# placa_potencia.net
KiCad netlist of a schematic drawn in EAGLE
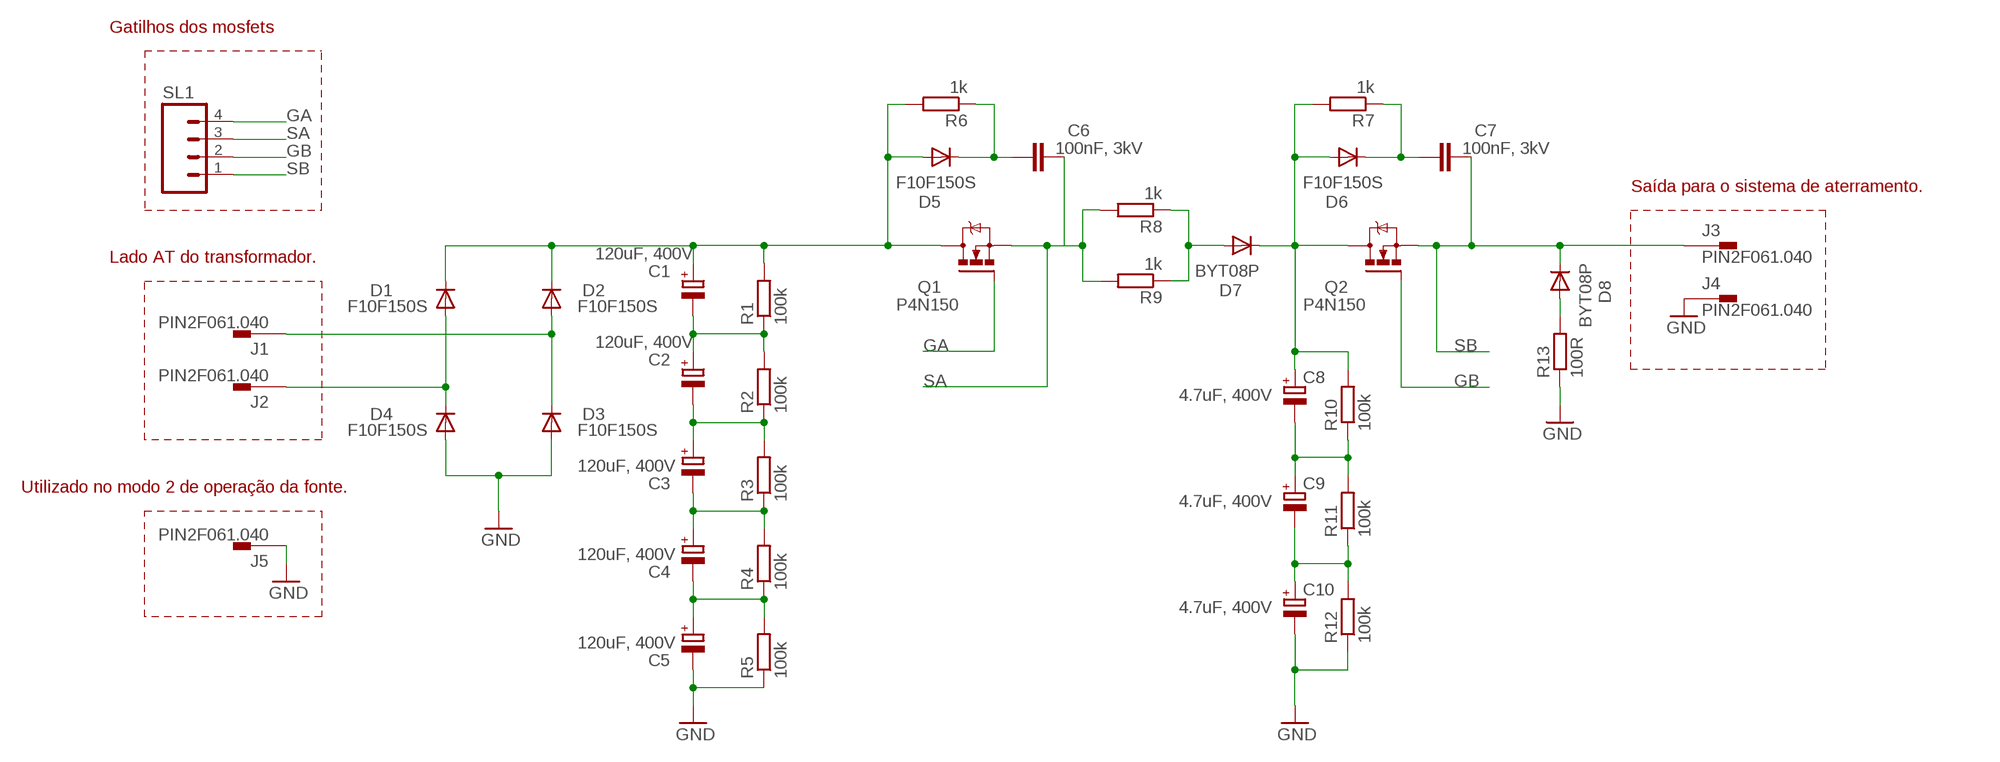
[diagram p0: schematic, sheet 1]

(export (version "E")
  (design (tool "Eeschema 10.0.6"))
  (components
    (comp (ref "C1")
      (value "120uF, 400V")
      (footprint "eagle-import:E7,5-16")
      (libsource (lib "eagle-import") (part "CPOL-EUE7.5-16"))
    )
    (comp (ref "C2")
      (value "120uF, 400V")
      (footprint "eagle-import:E7,5-16")
      (libsource (lib "eagle-import") (part "CPOL-EUE7.5-16"))
    )
    (comp (ref "C3")
      (value "120uF, 400V")
      (footprint "eagle-import:E7,5-16")
      (libsource (lib "eagle-import") (part "CPOL-EUE7.5-16"))
    )
    (comp (ref "C4")
      (value "120uF, 400V")
      (footprint "eagle-import:E7,5-16")
      (libsource (lib "eagle-import") (part "CPOL-EUE7.5-16"))
    )
    (comp (ref "C5")
      (value "120uF, 400V")
      (footprint "eagle-import:E7,5-16")
      (libsource (lib "eagle-import") (part "CPOL-EUE7.5-16"))
    )
    (comp (ref "C6")
      (value "100nF, 3kV")
      (footprint "eagle-import:C050-035X075")
      (libsource (lib "eagle-import") (part "C-EU050-035X075"))
    )
    (comp (ref "C7")
      (value "100nF, 3kV")
      (footprint "eagle-import:C050-035X075")
      (libsource (lib "eagle-import") (part "C-EU050-035X075"))
    )
    (comp (ref "C8")
      (value "4.7uF, 400V")
      (footprint "eagle-import:E5-8,5")
      (libsource (lib "eagle-import") (part "CPOL-EUE5-8.5"))
    )
    (comp (ref "C9")
      (value "4.7uF, 400V")
      (footprint "eagle-import:E5-8,5")
      (libsource (lib "eagle-import") (part "CPOL-EUE5-8.5"))
    )
    (comp (ref "C10")
      (value "4.7uF, 400V")
      (footprint "eagle-import:E5-8,5")
      (libsource (lib "eagle-import") (part "CPOL-EUE5-8.5"))
    )
    (comp (ref "D1")
      (value "F10F150S")
      (footprint "eagle-import:TO220ACS")
      (libsource (lib "eagle-import") (part "BYT08P"))
    )
    (comp (ref "D2")
      (value "F10F150S")
      (footprint "eagle-import:TO220ACS")
      (libsource (lib "eagle-import") (part "BYT08P"))
    )
    (comp (ref "D3")
      (value "F10F150S")
      (footprint "eagle-import:TO220ACS")
      (libsource (lib "eagle-import") (part "BYT08P"))
    )
    (comp (ref "D4")
      (value "F10F150S")
      (footprint "eagle-import:TO220ACS")
      (libsource (lib "eagle-import") (part "BYT08P"))
    )
    (comp (ref "D5")
      (value "F10F150S")
      (footprint "eagle-import:TO220ACS")
      (libsource (lib "eagle-import") (part "BYT08P"))
    )
    (comp (ref "D6")
      (value "F10F150S")
      (footprint "eagle-import:TO220ACS")
      (libsource (lib "eagle-import") (part "BYT08P"))
    )
    (comp (ref "D7")
      (value "BYT08P")
      (footprint "eagle-import:TO220ACS")
      (libsource (lib "eagle-import") (part "BYT08P"))
    )
    (comp (ref "D8")
      (value "BYT08P")
      (footprint "eagle-import:TO220ACS")
      (libsource (lib "eagle-import") (part "BYT08P"))
    )
    (comp (ref "J1")
      (value "PIN2F061.040")
      (footprint "eagle-import:F061.040")
      (libsource (lib "eagle-import") (part "PIN2F061.040"))
    )
    (comp (ref "J2")
      (value "PIN2F061.040")
      (footprint "eagle-import:F061.040")
      (libsource (lib "eagle-import") (part "PIN2F061.040"))
    )
    (comp (ref "J3")
      (value "PIN2F061.040")
      (footprint "eagle-import:F061.040")
      (libsource (lib "eagle-import") (part "PIN2F061.040"))
    )
    (comp (ref "J4")
      (value "PIN2F061.040")
      (footprint "eagle-import:F061.040")
      (libsource (lib "eagle-import") (part "PIN2F061.040"))
    )
    (comp (ref "J5")
      (value "PIN2F061.040")
      (footprint "eagle-import:F061.040")
      (libsource (lib "eagle-import") (part "PIN2F061.040"))
    )
    (comp (ref "Q1")
      (value "P4N150")
      (footprint "eagle-import:TO220BV")
      (libsource (lib "eagle-import") (part "IRF520"))
    )
    (comp (ref "Q2")
      (value "P4N150")
      (footprint "eagle-import:TO220BV")
      (libsource (lib "eagle-import") (part "IRF520"))
    )
    (comp (ref "R1")
      (value "100k")
      (footprint "eagle-import:0617_22")
      (libsource (lib "eagle-import") (part "R-EU_0617/22"))
    )
    (comp (ref "R2")
      (value "100k")
      (footprint "eagle-import:0617_22")
      (libsource (lib "eagle-import") (part "R-EU_0617/22"))
    )
    (comp (ref "R3")
      (value "100k")
      (footprint "eagle-import:0617_22")
      (libsource (lib "eagle-import") (part "R-EU_0617/22"))
    )
    (comp (ref "R4")
      (value "100k")
      (footprint "eagle-import:0617_22")
      (libsource (lib "eagle-import") (part "R-EU_0617/22"))
    )
    (comp (ref "R5")
      (value "100k")
      (footprint "eagle-import:0617_22")
      (libsource (lib "eagle-import") (part "R-EU_0617/22"))
    )
    (comp (ref "R6")
      (value "1k")
      (footprint "eagle-import:0617_22")
      (libsource (lib "eagle-import") (part "R-EU_0617/22"))
    )
    (comp (ref "R7")
      (value "1k")
      (footprint "eagle-import:0617_22")
      (libsource (lib "eagle-import") (part "R-EU_0617/22"))
    )
    (comp (ref "R8")
      (value "1k")
      (footprint "eagle-import:0617_22")
      (libsource (lib "eagle-import") (part "R-EU_0617/22"))
    )
    (comp (ref "R9")
      (value "1k")
      (footprint "eagle-import:0617_22")
      (libsource (lib "eagle-import") (part "R-EU_0617/22"))
    )
    (comp (ref "R10")
      (value "100k")
      (footprint "eagle-import:0617_22")
      (libsource (lib "eagle-import") (part "R-EU_0617/22"))
    )
    (comp (ref "R11")
      (value "100k")
      (footprint "eagle-import:0617_22")
      (libsource (lib "eagle-import") (part "R-EU_0617/22"))
    )
    (comp (ref "R12")
      (value "100k")
      (footprint "eagle-import:0617_22")
      (libsource (lib "eagle-import") (part "R-EU_0617/22"))
    )
    (comp (ref "R13")
      (value "100R")
      (footprint "eagle-import:0617_22")
      (libsource (lib "eagle-import") (part "R-EU_0617/22"))
    )
    (comp (ref "SL1")
      (value "M04")
      (footprint "eagle-import:04P")
      (libsource (lib "eagle-import") (part "M04"))
    )
  )
  (nets
    (net (code "1") (name "/GA") (class "Default")
      (node (ref "Q1") (pin "G") (pinfunction "G_G") (pintype "passive"))
      (node (ref "SL1") (pin "4") (pinfunction "4_4") (pintype "passive"))
    )
    (net (code "2") (name "/GB") (class "Default")
      (node (ref "Q2") (pin "G") (pinfunction "G_G") (pintype "passive"))
      (node (ref "SL1") (pin "2") (pinfunction "2_2") (pintype "passive"))
    )
    (net (code "3") (name "/SA") (class "Default")
      (node (ref "C6") (pin "2") (pinfunction "2_2") (pintype "passive"))
      (node (ref "Q1") (pin "S") (pinfunction "S_S") (pintype "passive"))
      (node (ref "R8") (pin "2") (pinfunction "2_2") (pintype "passive"))
      (node (ref "R9") (pin "2") (pinfunction "2_2") (pintype "passive"))
      (node (ref "SL1") (pin "3") (pinfunction "3_3") (pintype "passive"))
    )
    (net (code "4") (name "/SB") (class "Default")
      (node (ref "C7") (pin "2") (pinfunction "2_2") (pintype "passive"))
      (node (ref "D8") (pin "C") (pinfunction "C_C") (pintype "passive"))
      (node (ref "J3") (pin "A1") (pinfunction "1_A1") (pintype "passive"))
      (node (ref "J3") (pin "A2") (pinfunction "1_A2") (pintype "passive"))
      (node (ref "Q2") (pin "S") (pinfunction "S_S") (pintype "passive"))
      (node (ref "SL1") (pin "1") (pinfunction "1_1") (pintype "passive"))
    )
    (net (code "5") (name "GND") (class "Default")
      (node (ref "C10") (pin "-") (pinfunction "-_-") (pintype "passive"))
      (node (ref "C5") (pin "-") (pinfunction "-_-") (pintype "passive"))
      (node (ref "D3") (pin "A") (pinfunction "A_A") (pintype "passive"))
      (node (ref "D4") (pin "A") (pinfunction "A_A") (pintype "passive"))
      (node (ref "J4") (pin "A1") (pinfunction "1_A1") (pintype "passive"))
      (node (ref "J4") (pin "A2") (pinfunction "1_A2") (pintype "passive"))
      (node (ref "J5") (pin "A1") (pinfunction "1_A1") (pintype "passive"))
      (node (ref "J5") (pin "A2") (pinfunction "1_A2") (pintype "passive"))
      (node (ref "R12") (pin "1") (pinfunction "1_1") (pintype "passive"))
      (node (ref "R13") (pin "1") (pinfunction "1_1") (pintype "passive"))
      (node (ref "R5") (pin "1") (pinfunction "1_1") (pintype "passive"))
    )
    (net (code "6") (name "Net-(C1-Pad+)") (class "Default")
      (node (ref "C1") (pin "+") (pinfunction "+_+") (pintype "passive"))
      (node (ref "D1") (pin "C") (pinfunction "C_C") (pintype "passive"))
      (node (ref "D2") (pin "C") (pinfunction "C_C") (pintype "passive"))
      (node (ref "D5") (pin "A") (pinfunction "A_A") (pintype "passive"))
      (node (ref "Q1") (pin "D") (pinfunction "D_D") (pintype "passive"))
      (node (ref "R1") (pin "2") (pinfunction "2_2") (pintype "passive"))
      (node (ref "R6") (pin "2") (pinfunction "2_2") (pintype "passive"))
    )
    (net (code "7") (name "Net-(C1-Pad-)") (class "Default")
      (node (ref "C1") (pin "-") (pinfunction "-_-") (pintype "passive"))
      (node (ref "C2") (pin "+") (pinfunction "+_+") (pintype "passive"))
      (node (ref "R1") (pin "1") (pinfunction "1_1") (pintype "passive"))
      (node (ref "R2") (pin "2") (pinfunction "2_2") (pintype "passive"))
    )
    (net (code "8") (name "Net-(C2-Pad-)") (class "Default")
      (node (ref "C2") (pin "-") (pinfunction "-_-") (pintype "passive"))
      (node (ref "C3") (pin "+") (pinfunction "+_+") (pintype "passive"))
      (node (ref "R2") (pin "1") (pinfunction "1_1") (pintype "passive"))
      (node (ref "R3") (pin "2") (pinfunction "2_2") (pintype "passive"))
    )
    (net (code "9") (name "Net-(C3-Pad-)") (class "Default")
      (node (ref "C3") (pin "-") (pinfunction "-_-") (pintype "passive"))
      (node (ref "C4") (pin "+") (pinfunction "+_+") (pintype "passive"))
      (node (ref "R3") (pin "1") (pinfunction "1_1") (pintype "passive"))
      (node (ref "R4") (pin "2") (pinfunction "2_2") (pintype "passive"))
    )
    (net (code "10") (name "Net-(C4-Pad-)") (class "Default")
      (node (ref "C4") (pin "-") (pinfunction "-_-") (pintype "passive"))
      (node (ref "C5") (pin "+") (pinfunction "+_+") (pintype "passive"))
      (node (ref "R4") (pin "1") (pinfunction "1_1") (pintype "passive"))
      (node (ref "R5") (pin "2") (pinfunction "2_2") (pintype "passive"))
    )
    (net (code "11") (name "Net-(C6-Pad1)") (class "Default")
      (node (ref "C6") (pin "1") (pinfunction "1_1") (pintype "passive"))
      (node (ref "D5") (pin "C") (pinfunction "C_C") (pintype "passive"))
      (node (ref "R6") (pin "1") (pinfunction "1_1") (pintype "passive"))
    )
    (net (code "12") (name "Net-(C7-Pad1)") (class "Default")
      (node (ref "C7") (pin "1") (pinfunction "1_1") (pintype "passive"))
      (node (ref "D6") (pin "C") (pinfunction "C_C") (pintype "passive"))
      (node (ref "R7") (pin "1") (pinfunction "1_1") (pintype "passive"))
    )
    (net (code "13") (name "Net-(C8-Pad+)") (class "Default")
      (node (ref "C8") (pin "+") (pinfunction "+_+") (pintype "passive"))
      (node (ref "D6") (pin "A") (pinfunction "A_A") (pintype "passive"))
      (node (ref "D7") (pin "C") (pinfunction "C_C") (pintype "passive"))
      (node (ref "Q2") (pin "D") (pinfunction "D_D") (pintype "passive"))
      (node (ref "R10") (pin "2") (pinfunction "2_2") (pintype "passive"))
      (node (ref "R7") (pin "2") (pinfunction "2_2") (pintype "passive"))
    )
    (net (code "14") (name "Net-(C8-Pad-)") (class "Default")
      (node (ref "C8") (pin "-") (pinfunction "-_-") (pintype "passive"))
      (node (ref "C9") (pin "+") (pinfunction "+_+") (pintype "passive"))
      (node (ref "R10") (pin "1") (pinfunction "1_1") (pintype "passive"))
      (node (ref "R11") (pin "2") (pinfunction "2_2") (pintype "passive"))
    )
    (net (code "15") (name "Net-(C10-Pad+)") (class "Default")
      (node (ref "C10") (pin "+") (pinfunction "+_+") (pintype "passive"))
      (node (ref "C9") (pin "-") (pinfunction "-_-") (pintype "passive"))
      (node (ref "R11") (pin "1") (pinfunction "1_1") (pintype "passive"))
      (node (ref "R12") (pin "2") (pinfunction "2_2") (pintype "passive"))
    )
    (net (code "16") (name "Net-(D1-PadA)") (class "Default")
      (node (ref "D1") (pin "A") (pinfunction "A_A") (pintype "passive"))
      (node (ref "D4") (pin "C") (pinfunction "C_C") (pintype "passive"))
      (node (ref "J2") (pin "A1") (pinfunction "1_A1") (pintype "passive"))
      (node (ref "J2") (pin "A2") (pinfunction "1_A2") (pintype "passive"))
    )
    (net (code "17") (name "Net-(D2-PadA)") (class "Default")
      (node (ref "D2") (pin "A") (pinfunction "A_A") (pintype "passive"))
      (node (ref "D3") (pin "C") (pinfunction "C_C") (pintype "passive"))
      (node (ref "J1") (pin "A1") (pinfunction "1_A1") (pintype "passive"))
      (node (ref "J1") (pin "A2") (pinfunction "1_A2") (pintype "passive"))
    )
    (net (code "18") (name "Net-(D7-PadA)") (class "Default")
      (node (ref "D7") (pin "A") (pinfunction "A_A") (pintype "passive"))
      (node (ref "R8") (pin "1") (pinfunction "1_1") (pintype "passive"))
      (node (ref "R9") (pin "1") (pinfunction "1_1") (pintype "passive"))
    )
    (net (code "19") (name "Net-(D8-PadA)") (class "Default")
      (node (ref "D8") (pin "A") (pinfunction "A_A") (pintype "passive"))
      (node (ref "R13") (pin "2") (pinfunction "2_2") (pintype "passive"))
    )
  )
)
